# SCH.net
KiCad netlist of a schematic drawn in EasyEDA
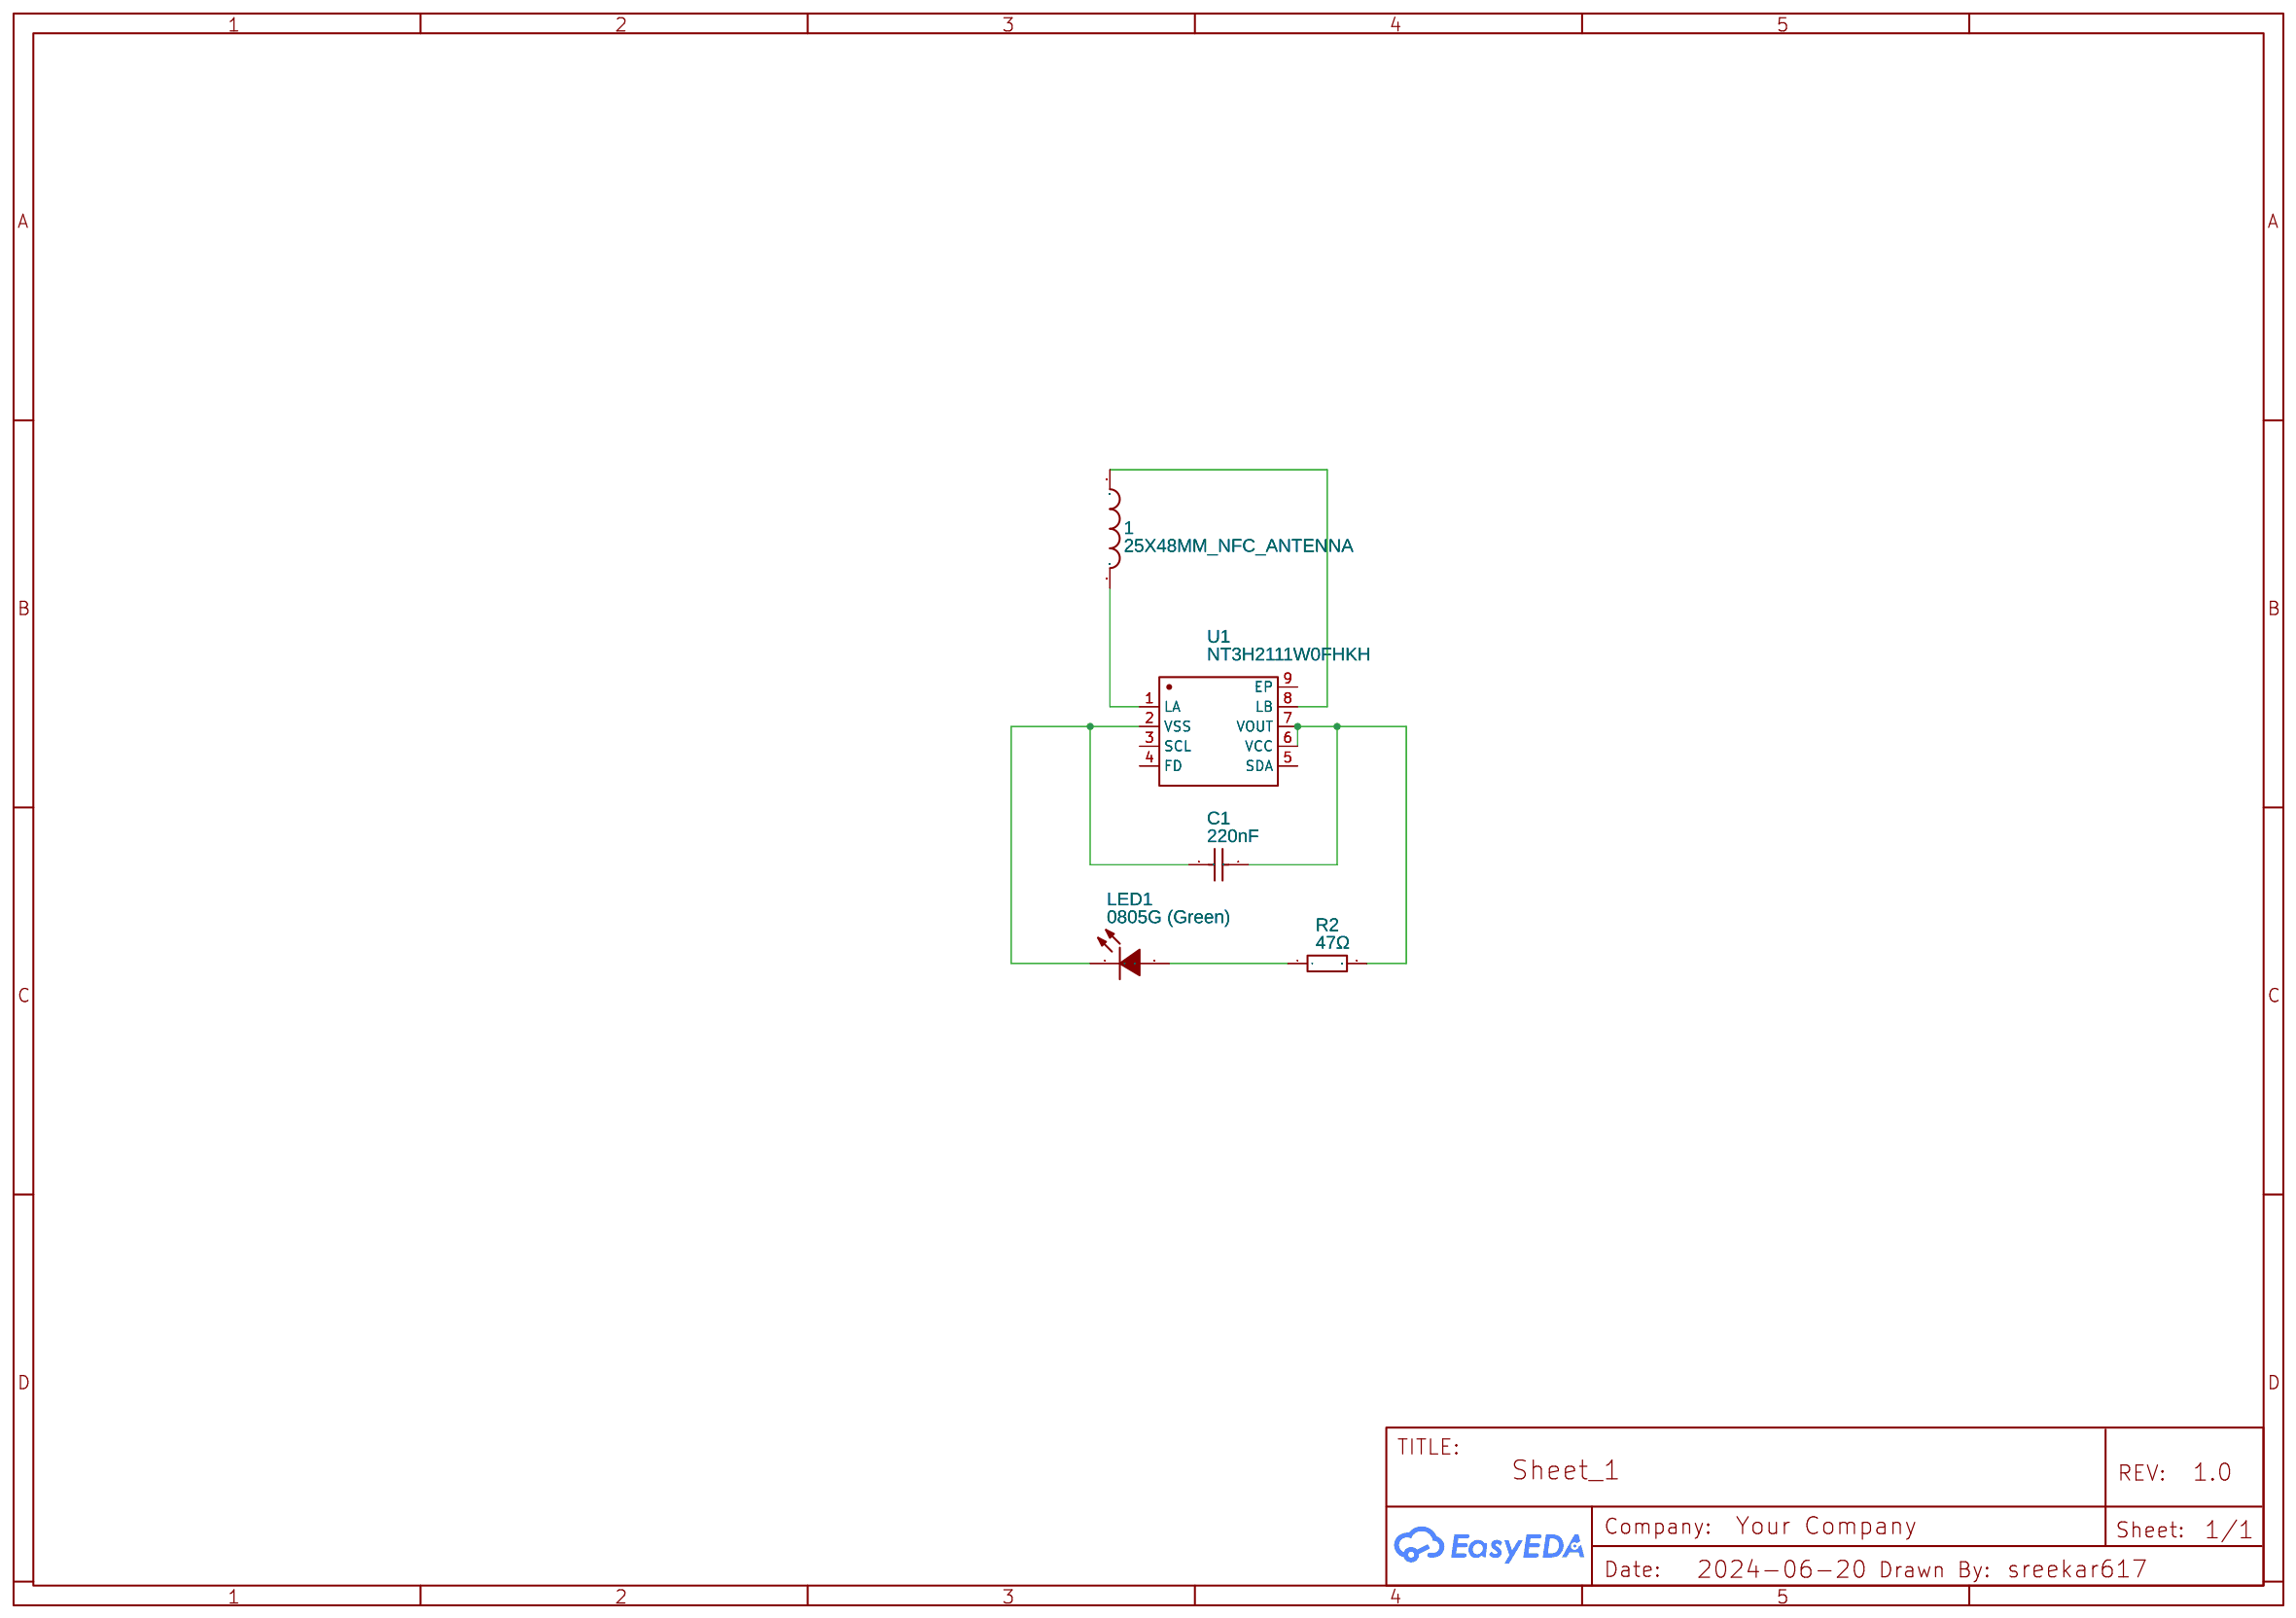
[diagram p0: schematic sheet]

(export (version "E")
  (design (tool "Eeschema 10.0.6"))
  (components
    (comp (ref "1") (value "25X48MM_NFC_ANTENNA") (libsource (lib "") (part "25X48MM_NFC_ANTENNA")))
    (comp (ref "C1")
      (value "220nF")
      (fields
        (field (name "Manufacturer Part") "CL10B224KA8NNNC")
        (field (name "Manufacturer") "SAMSUNG(三星)")
      )
      (libsource (lib "") (part "CL10B224KA8NNNC"))
    )
    (comp (ref "LED1")
      (value "0805G (Green)")
      (fields (field (name "Manufacturer Part") "KT-0805G") (field (name "Manufacturer") "KENTO"))
      (libsource (lib "") (part "0805G (Green)"))
    )
    (comp (ref "R2")
      (value "47Ω")
      (fields
        (field (name "Manufacturer Part") "0603WAF470JT5E")
        (field (name "Manufacturer") "UNI-ROYAL(厚声)")
      )
      (libsource (lib "") (part "0603WAF470JT5E"))
    )
    (comp (ref "U1")
      (value "NT3H2111W0FHKH")
      (fields (field (name "Manufacturer") "NXP(恩智浦)"))
      (libsource (lib "") (part "NT3H2111W0FHKH"))
    )
  )
  (nets
    (net (code "1") (name "Net-(LED1-A)") (class "Default")
      (node (ref "LED1") (pin "1") (pinfunction "A_1") (pintype "unspecified"))
      (node (ref "R2") (pin "1") (pinfunction "1_1") (pintype "input"))
    )
    (net (code "2") (name "Net-(LED1-K)") (class "Default")
      (node (ref "C1") (pin "1") (pinfunction "1_1") (pintype "input"))
      (node (ref "LED1") (pin "2") (pinfunction "K_2") (pintype "unspecified"))
      (node (ref "U1") (pin "2") (pinfunction "VSS_2") (pintype "unspecified"))
    )
    (net (code "3") (name "Net-(U1-LA)") (class "Default")
      (node (ref "1") (pin "P$2") (pinfunction "P$2_P$2") (pintype "bidirectional"))
      (node (ref "U1") (pin "1") (pinfunction "LA_1") (pintype "unspecified"))
    )
    (net (code "4") (name "Net-(U1-LB)") (class "Default")
      (node (ref "1") (pin "P$1") (pinfunction "P$1_P$1") (pintype "bidirectional"))
      (node (ref "U1") (pin "8") (pinfunction "LB_8") (pintype "unspecified"))
    )
    (net (code "5") (name "Net-(U1-VCC)") (class "Default")
      (node (ref "C1") (pin "2") (pinfunction "2_2") (pintype "input"))
      (node (ref "R2") (pin "2") (pinfunction "2_2") (pintype "input"))
      (node (ref "U1") (pin "6") (pinfunction "VCC_6") (pintype "unspecified"))
      (node (ref "U1") (pin "7") (pinfunction "VOUT_7") (pintype "unspecified"))
    )
    (net (code "6") (name "unconnected-(U1-EP-Pad9)") (class "Default")
      (node (ref "U1") (pin "9") (pinfunction "EP_9") (pintype "unspecified"))
    )
    (net (code "7") (name "unconnected-(U1-FD-Pad4)") (class "Default")
      (node (ref "U1") (pin "4") (pinfunction "FD_4") (pintype "unspecified"))
    )
    (net (code "8") (name "unconnected-(U1-SCL-Pad3)") (class "Default")
      (node (ref "U1") (pin "3") (pinfunction "SCL_3") (pintype "unspecified"))
    )
    (net (code "9") (name "unconnected-(U1-SDA-Pad5)") (class "Default")
      (node (ref "U1") (pin "5") (pinfunction "SDA_5") (pintype "unspecified"))
    )
  )
)
